# sensors.net
KiCad netlist of a schematic drawn in EAGLE
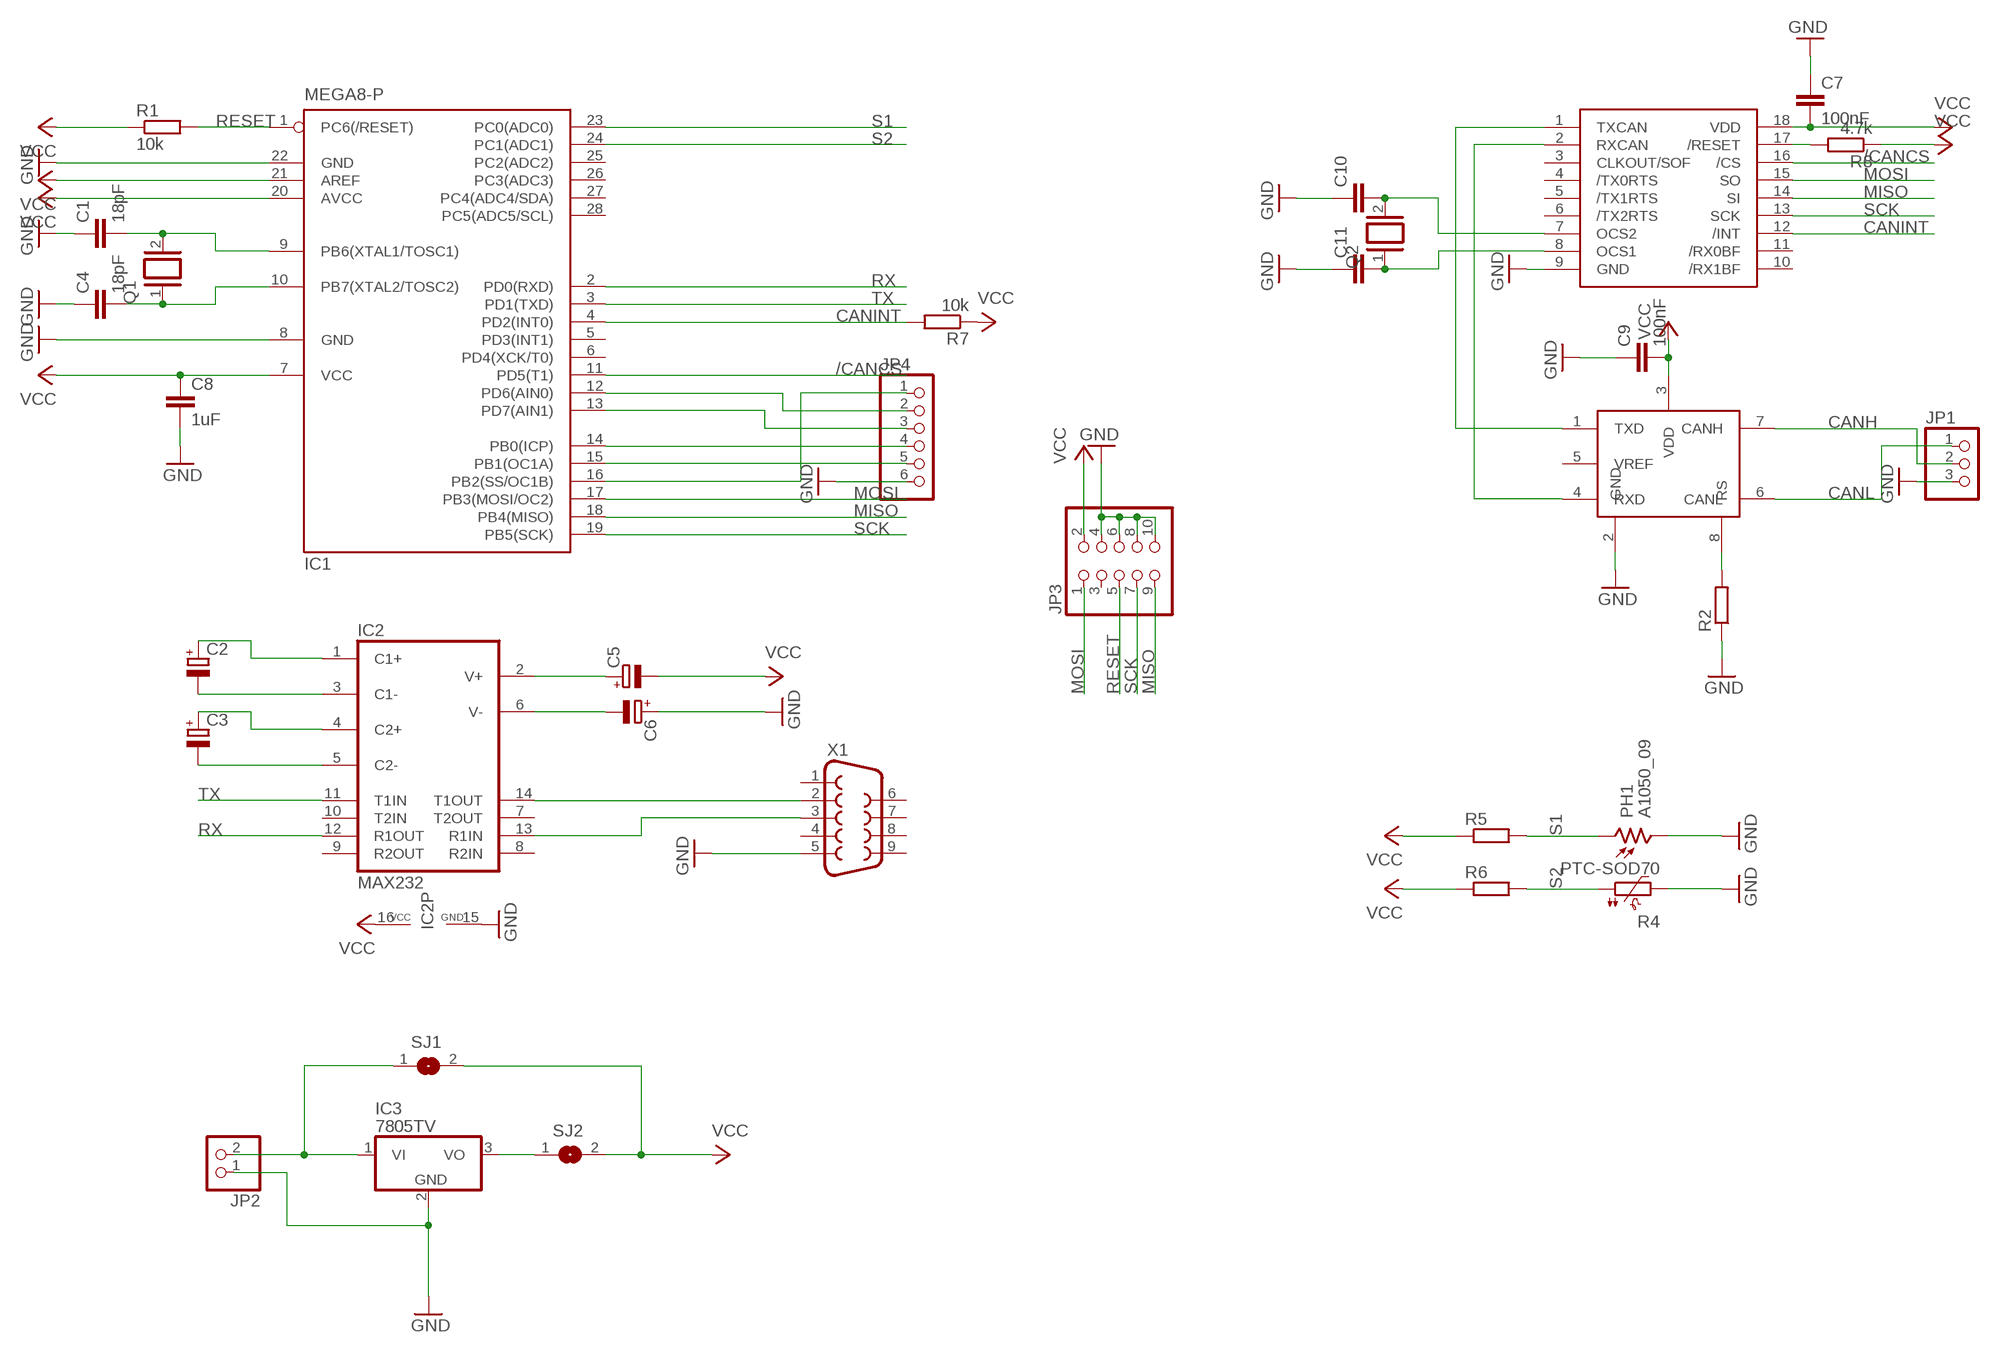
[diagram p0: schematic, sheet 1]

(export (version "E")
  (design (tool "Eeschema 10.0.6"))
  (components
    (comp (ref "C1")
      (value "18pF")
      (footprint "eagle-import:C025-024X044")
      (libsource (lib "eagle-import") (part "resistor_C-EU025-024X044"))
    )
    (comp (ref "C2")
      (value "CPOL-EUE3.5-8")
      (footprint "eagle-import:E3,5-8")
      (libsource (lib "eagle-import") (part "CPOL-EUE3.5-8"))
    )
    (comp (ref "C3")
      (value "CPOL-EUE3.5-8")
      (footprint "eagle-import:E3,5-8")
      (libsource (lib "eagle-import") (part "CPOL-EUE3.5-8"))
    )
    (comp (ref "C4")
      (value "18pF")
      (footprint "eagle-import:C025-024X044")
      (libsource (lib "eagle-import") (part "resistor_C-EU025-024X044"))
    )
    (comp (ref "C5")
      (value "CPOL-EUE3.5-8")
      (footprint "eagle-import:E3,5-8")
      (libsource (lib "eagle-import") (part "CPOL-EUE3.5-8"))
    )
    (comp (ref "C6")
      (value "CPOL-EUE3.5-8")
      (footprint "eagle-import:E3,5-8")
      (libsource (lib "eagle-import") (part "CPOL-EUE3.5-8"))
    )
    (comp (ref "C7")
      (value "100nF")
      (footprint "eagle-import:C0603")
      (libsource (lib "eagle-import") (part "C-EUC0603"))
    )
    (comp (ref "C8")
      (value "1uF")
      (footprint "eagle-import:C0603")
      (libsource (lib "eagle-import") (part "C-EUC0603"))
    )
    (comp (ref "C9")
      (value "100nF")
      (footprint "eagle-import:C0603")
      (libsource (lib "eagle-import") (part "C-EUC0603"))
    )
    (comp (ref "C10")
      (value "C-EUC0603")
      (footprint "eagle-import:C0603")
      (libsource (lib "eagle-import") (part "C-EUC0603"))
    )
    (comp (ref "C11")
      (value "C-EUC0603")
      (footprint "eagle-import:C0603")
      (libsource (lib "eagle-import") (part "C-EUC0603"))
    )
    (comp (ref "IC1")
      (value "MEGA8-P")
      (footprint "eagle-import:DIL28-3")
      (libsource (lib "eagle-import") (part "MEGA8-P"))
    )
    (comp (ref "IC2")
      (value "MAX232")
      (footprint "eagle-import:DIL16")
      (fields (field (name "MF") "MAXIM") (field (name "MPN") "MAX232ACPE+"))
      (libsource (lib "eagle-import") (part "MAX232"))
    )
    (comp (ref "IC3")
      (value "7805TV")
      (footprint "eagle-import:TO220V")
      (libsource (lib "eagle-import") (part "78TV05"))
    )
    (comp (ref "JP1")
      (value "PINHD-1X3")
      (footprint "eagle-import:1X03")
      (libsource (lib "eagle-import") (part "PINHD-1X3"))
    )
    (comp (ref "JP2")
      (value "PINHD-1X2")
      (footprint "eagle-import:1X02")
      (libsource (lib "eagle-import") (part "PINHD-1X2"))
    )
    (comp (ref "JP3")
      (value "PINHD-2X5")
      (footprint "eagle-import:2X05")
      (libsource (lib "eagle-import") (part "PINHD-2X5"))
    )
    (comp (ref "JP4")
      (value "PINHD-1X6")
      (footprint "eagle-import:1X06")
      (libsource (lib "eagle-import") (part "PINHD-1X6"))
    )
    (comp (ref "PH1")
      (value "A1050_09")
      (footprint "eagle-import:T0-46-A10XX")
      (libsource (lib "eagle-import") (part "A1050_09"))
    )
    (comp (ref "Q1")
      (value "XTAL/S")
      (footprint "eagle-import:QS")
      (libsource (lib "eagle-import") (part "XTAL/S"))
    )
    (comp (ref "Q2")
      (value "XTAL/S")
      (footprint "eagle-import:QS")
      (libsource (lib "eagle-import") (part "XTAL/S"))
    )
    (comp (ref "R1")
      (value "10k")
      (footprint "eagle-import:0207_10")
      (libsource (lib "eagle-import") (part "resistor_R-EU_0207/10"))
    )
    (comp (ref "R2")
      (value "R-EU_0207/10")
      (footprint "eagle-import:0207_10")
      (libsource (lib "eagle-import") (part "resistor_R-EU_0207/10"))
    )
    (comp (ref "R4")
      (value "PTC-SOD70")
      (footprint "eagle-import:SOD70")
      (libsource (lib "eagle-import") (part "PTC-SOD70"))
    )
    (comp (ref "R5")
      (value "R-EU_0207/10")
      (footprint "eagle-import:0207_10")
      (libsource (lib "eagle-import") (part "R-EU_0207/10"))
    )
    (comp (ref "R6")
      (value "R-EU_0207/10")
      (footprint "eagle-import:0207_10")
      (libsource (lib "eagle-import") (part "R-EU_0207/10"))
    )
    (comp (ref "R7")
      (value "10k")
      (footprint "eagle-import:0207_10")
      (libsource (lib "eagle-import") (part "resistor_R-EU_0207/10"))
    )
    (comp (ref "R8")
      (value "4.7k")
      (footprint "eagle-import:0207_10")
      (libsource (lib "eagle-import") (part "R-EU_0207/10"))
    )
    (comp (ref "SJ1") (value "SJ") (footprint "eagle-import:SJ") (libsource (lib "eagle-import") (part "SJ")))
    (comp (ref "SJ2") (value "SJ") (footprint "eagle-import:SJ") (libsource (lib "eagle-import") (part "SJ")))
    (comp (ref "U$1")
      (value "MCP251518-LEAD_SOIC")
      (footprint "eagle-import:SOIC18L")
      (libsource (lib "eagle-import") (part "MCP251518-LEAD_SOIC"))
    )
    (comp (ref "U$2")
      (value "MCP2551DIL8")
      (footprint "eagle-import:DIL8")
      (libsource (lib "eagle-import") (part "MCP2551DIL8"))
    )
    (comp (ref "X1")
      (value "F09HP")
      (footprint "eagle-import:F09HP")
      (libsource (lib "eagle-import") (part "F09HP"))
    )
  )
  (nets
    (net (code "1") (name "/CANH") (class "Default")
      (node (ref "JP1") (pin "2") (pinfunction "2_2") (pintype "passive"))
      (node (ref "U$2") (pin "7") (pinfunction "CANH_7") (pintype "bidirectional"))
    )
    (net (code "2") (name "/CANINT") (class "Default")
      (node (ref "IC1") (pin "4") (pinfunction "PD2(INT0)_4") (pintype "bidirectional"))
      (node (ref "R7") (pin "2") (pinfunction "2_2") (pintype "passive"))
      (node (ref "U$1") (pin "12") (pinfunction "/INT_12") (pintype "bidirectional"))
    )
    (net (code "3") (name "/CANL") (class "Default")
      (node (ref "JP1") (pin "1") (pinfunction "1_1") (pintype "passive"))
      (node (ref "U$2") (pin "6") (pinfunction "CANL_6") (pintype "bidirectional"))
    )
    (net (code "4") (name "/MISO") (class "Default")
      (node (ref "IC1") (pin "18") (pinfunction "PB4(MISO)_18") (pintype "bidirectional"))
      (node (ref "JP3") (pin "9") (pinfunction "9_9") (pintype "passive"))
      (node (ref "U$1") (pin "14") (pinfunction "SI_14") (pintype "bidirectional"))
    )
    (net (code "5") (name "/MOSI") (class "Default")
      (node (ref "IC1") (pin "17") (pinfunction "PB3(MOSI/OC2)_17") (pintype "bidirectional"))
      (node (ref "JP3") (pin "1") (pinfunction "1_1") (pintype "passive"))
      (node (ref "U$1") (pin "15") (pinfunction "SO_15") (pintype "bidirectional"))
    )
    (net (code "6") (name "/RESET") (class "Default")
      (node (ref "IC1") (pin "1") (pinfunction "PC6(/RESET)_1") (pintype "bidirectional"))
      (node (ref "JP3") (pin "5") (pinfunction "5_5") (pintype "passive"))
      (node (ref "R1") (pin "2") (pinfunction "2_2") (pintype "passive"))
    )
    (net (code "7") (name "/RX") (class "Default")
      (node (ref "IC1") (pin "2") (pinfunction "PD0(RXD)_2") (pintype "bidirectional"))
      (node (ref "IC2") (pin "12") (pinfunction "R1OUT_12") (pintype "output"))
    )
    (net (code "8") (name "/S1") (class "Default")
      (node (ref "IC1") (pin "23") (pinfunction "PC0(ADC0)_23") (pintype "bidirectional"))
      (node (ref "PH1") (pin "1") (pinfunction "1_1") (pintype "passive"))
      (node (ref "R5") (pin "2") (pinfunction "2_2") (pintype "passive"))
    )
    (net (code "9") (name "/S2") (class "Default")
      (node (ref "IC1") (pin "24") (pinfunction "PC1(ADC1)_24") (pintype "bidirectional"))
      (node (ref "R4") (pin "1") (pinfunction "1_1") (pintype "passive"))
      (node (ref "R6") (pin "2") (pinfunction "2_2") (pintype "passive"))
    )
    (net (code "10") (name "/SCK") (class "Default")
      (node (ref "IC1") (pin "19") (pinfunction "PB5(SCK)_19") (pintype "bidirectional"))
      (node (ref "JP3") (pin "7") (pinfunction "7_7") (pintype "passive"))
      (node (ref "U$1") (pin "13") (pinfunction "SCK_13") (pintype "bidirectional"))
    )
    (net (code "11") (name "/TX") (class "Default")
      (node (ref "IC1") (pin "3") (pinfunction "PD1(TXD)_3") (pintype "bidirectional"))
      (node (ref "IC2") (pin "11") (pinfunction "T1IN_11") (pintype "input"))
    )
    (net (code "12") (name "/{slash}CANCS") (class "Default")
      (node (ref "IC1") (pin "11") (pinfunction "PD5(T1)_11") (pintype "bidirectional"))
      (node (ref "U$1") (pin "16") (pinfunction "/CS_16") (pintype "bidirectional"))
    )
    (net (code "13") (name "GND") (class "Default")
      (node (ref "C1") (pin "1") (pinfunction "1_1") (pintype "passive"))
      (node (ref "C10") (pin "1") (pinfunction "1_1") (pintype "passive"))
      (node (ref "C11") (pin "1") (pinfunction "1_1") (pintype "passive"))
      (node (ref "C4") (pin "1") (pinfunction "1_1") (pintype "passive"))
      (node (ref "C6") (pin "+") (pinfunction "+_+") (pintype "passive"))
      (node (ref "C7") (pin "1") (pinfunction "1_1") (pintype "passive"))
      (node (ref "C8") (pin "2") (pinfunction "2_2") (pintype "passive"))
      (node (ref "C9") (pin "1") (pinfunction "1_1") (pintype "passive"))
      (node (ref "IC1") (pin "22") (pinfunction "GND_22") (pintype "power_in"))
      (node (ref "IC1") (pin "8") (pinfunction "GND_8") (pintype "power_in"))
      (node (ref "IC2") (pin "15") (pinfunction "GND_15") (pintype "power_in"))
      (node (ref "IC3") (pin "2") (pinfunction "GND_2") (pintype "passive"))
      (node (ref "JP1") (pin "3") (pinfunction "3_3") (pintype "passive"))
      (node (ref "JP2") (pin "1") (pinfunction "1_1") (pintype "passive"))
      (node (ref "JP3") (pin "10") (pinfunction "10_10") (pintype "passive"))
      (node (ref "JP3") (pin "4") (pinfunction "4_4") (pintype "passive"))
      (node (ref "JP3") (pin "6") (pinfunction "6_6") (pintype "passive"))
      (node (ref "JP3") (pin "8") (pinfunction "8_8") (pintype "passive"))
      (node (ref "JP4") (pin "6") (pinfunction "6_6") (pintype "passive"))
      (node (ref "PH1") (pin "2") (pinfunction "2_2") (pintype "passive"))
      (node (ref "R2") (pin "1") (pinfunction "1_1") (pintype "passive"))
      (node (ref "R4") (pin "2") (pinfunction "2_2") (pintype "passive"))
      (node (ref "U$1") (pin "9") (pinfunction "GND_9") (pintype "bidirectional"))
      (node (ref "U$2") (pin "2") (pinfunction "GND_2") (pintype "bidirectional"))
      (node (ref "X1") (pin "5") (pinfunction "5_5") (pintype "passive"))
    )
    (net (code "14") (name "Net-(IC1-PB0(ICP))") (class "Default")
      (node (ref "IC1") (pin "14") (pinfunction "PB0(ICP)_14") (pintype "bidirectional"))
      (node (ref "JP4") (pin "4") (pinfunction "4_4") (pintype "passive"))
    )
    (net (code "15") (name "Net-(IC1-PB1(OC1A))") (class "Default")
      (node (ref "IC1") (pin "15") (pinfunction "PB1(OC1A)_15") (pintype "bidirectional"))
      (node (ref "JP4") (pin "5") (pinfunction "5_5") (pintype "passive"))
    )
    (net (code "16") (name "Net-(IC1-PB2(SS{slash}OC1B))") (class "Default")
      (node (ref "IC1") (pin "16") (pinfunction "PB2(SS/OC1B)_16") (pintype "bidirectional"))
      (node (ref "JP4") (pin "1") (pinfunction "1_1") (pintype "passive"))
    )
    (net (code "17") (name "Net-(IC1-PB6(XTAL1{slash}TOSC1))") (class "Default")
      (node (ref "C1") (pin "2") (pinfunction "2_2") (pintype "passive"))
      (node (ref "IC1") (pin "9") (pinfunction "PB6(XTAL1/TOSC1)_9") (pintype "bidirectional"))
      (node (ref "Q1") (pin "2") (pinfunction "2_2") (pintype "passive"))
    )
    (net (code "18") (name "Net-(IC1-PB7(XTAL2{slash}TOSC2))") (class "Default")
      (node (ref "C4") (pin "2") (pinfunction "2_2") (pintype "passive"))
      (node (ref "IC1") (pin "10") (pinfunction "PB7(XTAL2/TOSC2)_10") (pintype "bidirectional"))
      (node (ref "Q1") (pin "1") (pinfunction "1_1") (pintype "passive"))
    )
    (net (code "19") (name "Net-(IC1-PD6(AIN0))") (class "Default")
      (node (ref "IC1") (pin "12") (pinfunction "PD6(AIN0)_12") (pintype "bidirectional"))
      (node (ref "JP4") (pin "2") (pinfunction "2_2") (pintype "passive"))
    )
    (net (code "20") (name "Net-(IC1-PD7(AIN1))") (class "Default")
      (node (ref "IC1") (pin "13") (pinfunction "PD7(AIN1)_13") (pintype "bidirectional"))
      (node (ref "JP4") (pin "3") (pinfunction "3_3") (pintype "passive"))
    )
    (net (code "21") (name "Net-(IC2A-C1+)") (class "Default")
      (node (ref "C2") (pin "+") (pinfunction "+_+") (pintype "passive"))
      (node (ref "IC2") (pin "1") (pinfunction "C1+_1") (pintype "bidirectional"))
    )
    (net (code "22") (name "Net-(IC2A-C1-)") (class "Default")
      (node (ref "C2") (pin "-") (pinfunction "-_-") (pintype "passive"))
      (node (ref "IC2") (pin "3") (pinfunction "C1-_3") (pintype "bidirectional"))
    )
    (net (code "23") (name "Net-(IC2A-C2+)") (class "Default")
      (node (ref "C3") (pin "+") (pinfunction "+_+") (pintype "passive"))
      (node (ref "IC2") (pin "4") (pinfunction "C2+_4") (pintype "bidirectional"))
    )
    (net (code "24") (name "Net-(IC2A-C2-)") (class "Default")
      (node (ref "C3") (pin "-") (pinfunction "-_-") (pintype "passive"))
      (node (ref "IC2") (pin "5") (pinfunction "C2-_5") (pintype "bidirectional"))
    )
    (net (code "25") (name "Net-(IC2A-R1IN)") (class "Default")
      (node (ref "IC2") (pin "13") (pinfunction "R1IN_13") (pintype "input"))
      (node (ref "X1") (pin "3") (pinfunction "3_3") (pintype "passive"))
    )
    (net (code "26") (name "Net-(IC2A-T1OUT)") (class "Default")
      (node (ref "IC2") (pin "14") (pinfunction "T1OUT_14") (pintype "output"))
      (node (ref "X1") (pin "2") (pinfunction "2_2") (pintype "passive"))
    )
    (net (code "27") (name "Net-(IC2A-V+)") (class "Default")
      (node (ref "C5") (pin "+") (pinfunction "+_+") (pintype "passive"))
      (node (ref "IC2") (pin "2") (pinfunction "V+_2") (pintype "bidirectional"))
    )
    (net (code "28") (name "Net-(IC2A-V-)") (class "Default")
      (node (ref "C6") (pin "-") (pinfunction "-_-") (pintype "passive"))
      (node (ref "IC2") (pin "6") (pinfunction "V-_6") (pintype "bidirectional"))
    )
    (net (code "29") (name "Net-(IC3-VI)") (class "Default")
      (node (ref "IC3") (pin "1") (pinfunction "VI_1") (pintype "input"))
      (node (ref "JP2") (pin "2") (pinfunction "2_2") (pintype "passive"))
      (node (ref "SJ1") (pin "1") (pinfunction "1_1") (pintype "passive"))
    )
    (net (code "30") (name "Net-(IC3-VO)") (class "Default")
      (node (ref "IC3") (pin "3") (pinfunction "VO_3") (pintype "passive"))
      (node (ref "SJ2") (pin "1") (pinfunction "1_1") (pintype "passive"))
    )
    (net (code "31") (name "Net-(U$1-OCS1)") (class "Default")
      (node (ref "C11") (pin "2") (pinfunction "2_2") (pintype "passive"))
      (node (ref "Q2") (pin "1") (pinfunction "1_1") (pintype "passive"))
      (node (ref "U$1") (pin "8") (pinfunction "OCS1_8") (pintype "bidirectional"))
    )
    (net (code "32") (name "Net-(U$1-OCS2)") (class "Default")
      (node (ref "C10") (pin "2") (pinfunction "2_2") (pintype "passive"))
      (node (ref "Q2") (pin "2") (pinfunction "2_2") (pintype "passive"))
      (node (ref "U$1") (pin "7") (pinfunction "OCS2_7") (pintype "bidirectional"))
    )
    (net (code "33") (name "Net-(U$1-RXCAN)") (class "Default")
      (node (ref "U$1") (pin "2") (pinfunction "RXCAN_2") (pintype "bidirectional"))
      (node (ref "U$2") (pin "4") (pinfunction "RXD_4") (pintype "bidirectional"))
    )
    (net (code "34") (name "Net-(U$1-TXCAN)") (class "Default")
      (node (ref "U$1") (pin "1") (pinfunction "TXCAN_1") (pintype "bidirectional"))
      (node (ref "U$2") (pin "1") (pinfunction "TXD_1") (pintype "bidirectional"))
    )
    (net (code "35") (name "Net-(U$1-{slash}RESET)") (class "Default")
      (node (ref "R8") (pin "2") (pinfunction "2_2") (pintype "passive"))
      (node (ref "U$1") (pin "17") (pinfunction "/RESET_17") (pintype "bidirectional"))
    )
    (net (code "36") (name "Net-(U$2-RS)") (class "Default")
      (node (ref "R2") (pin "2") (pinfunction "2_2") (pintype "passive"))
      (node (ref "U$2") (pin "8") (pinfunction "RS_8") (pintype "bidirectional"))
    )
    (net (code "37") (name "VCC") (class "Default")
      (node (ref "C5") (pin "-") (pinfunction "-_-") (pintype "passive"))
      (node (ref "C7") (pin "2") (pinfunction "2_2") (pintype "passive"))
      (node (ref "C8") (pin "1") (pinfunction "1_1") (pintype "passive"))
      (node (ref "C9") (pin "2") (pinfunction "2_2") (pintype "passive"))
      (node (ref "IC1") (pin "20") (pinfunction "AVCC_20") (pintype "power_in"))
      (node (ref "IC1") (pin "21") (pinfunction "AREF_21") (pintype "passive"))
      (node (ref "IC1") (pin "7") (pinfunction "VCC_7") (pintype "power_in"))
      (node (ref "IC2") (pin "16") (pinfunction "VCC_16") (pintype "power_in"))
      (node (ref "JP3") (pin "2") (pinfunction "2_2") (pintype "passive"))
      (node (ref "R1") (pin "1") (pinfunction "1_1") (pintype "passive"))
      (node (ref "R5") (pin "1") (pinfunction "1_1") (pintype "passive"))
      (node (ref "R6") (pin "1") (pinfunction "1_1") (pintype "passive"))
      (node (ref "R7") (pin "1") (pinfunction "1_1") (pintype "passive"))
      (node (ref "R8") (pin "1") (pinfunction "1_1") (pintype "passive"))
      (node (ref "SJ1") (pin "2") (pinfunction "2_2") (pintype "passive"))
      (node (ref "SJ2") (pin "2") (pinfunction "2_2") (pintype "passive"))
      (node (ref "U$1") (pin "18") (pinfunction "VDD_18") (pintype "bidirectional"))
      (node (ref "U$2") (pin "3") (pinfunction "VDD_3") (pintype "bidirectional"))
    )
    (net (code "38") (name "unconnected-(IC1-PC2(ADC2)-Pad25)") (class "Default")
      (node (ref "IC1") (pin "25") (pinfunction "PC2(ADC2)_25") (pintype "bidirectional"))
    )
    (net (code "39") (name "unconnected-(IC1-PC3(ADC3)-Pad26)") (class "Default")
      (node (ref "IC1") (pin "26") (pinfunction "PC3(ADC3)_26") (pintype "bidirectional"))
    )
    (net (code "40") (name "unconnected-(IC1-PC4(ADC4{slash}SDA)-Pad27)") (class "Default")
      (node (ref "IC1") (pin "27") (pinfunction "PC4(ADC4/SDA)_27") (pintype "bidirectional"))
    )
    (net (code "41") (name "unconnected-(IC1-PC5(ADC5{slash}SCL)-Pad28)") (class "Default")
      (node (ref "IC1") (pin "28") (pinfunction "PC5(ADC5/SCL)_28") (pintype "bidirectional"))
    )
    (net (code "42") (name "unconnected-(IC1-PD3(INT1)-Pad5)") (class "Default")
      (node (ref "IC1") (pin "5") (pinfunction "PD3(INT1)_5") (pintype "bidirectional"))
    )
    (net (code "43") (name "unconnected-(IC1-PD4(XCK{slash}T0)-Pad6)") (class "Default")
      (node (ref "IC1") (pin "6") (pinfunction "PD4(XCK/T0)_6") (pintype "bidirectional"))
    )
    (net (code "44") (name "unconnected-(IC2A-R2IN-Pad8)") (class "Default")
      (node (ref "IC2") (pin "8") (pinfunction "R2IN_8") (pintype "input"))
    )
    (net (code "45") (name "unconnected-(IC2A-R2OUT-Pad9)") (class "Default")
      (node (ref "IC2") (pin "9") (pinfunction "R2OUT_9") (pintype "output"))
    )
    (net (code "46") (name "unconnected-(IC2A-T2IN-Pad10)") (class "Default")
      (node (ref "IC2") (pin "10") (pinfunction "T2IN_10") (pintype "input"))
    )
    (net (code "47") (name "unconnected-(IC2A-T2OUT-Pad7)") (class "Default")
      (node (ref "IC2") (pin "7") (pinfunction "T2OUT_7") (pintype "output"))
    )
    (net (code "48") (name "unconnected-(JP3-Pad3)") (class "Default")
      (node (ref "JP3") (pin "3") (pinfunction "3_3") (pintype "passive"))
    )
    (net (code "49") (name "unconnected-(U$1-CLKOUT{slash}SOF-Pad3)") (class "Default")
      (node (ref "U$1") (pin "3") (pinfunction "CLKOUT/SOF_3") (pintype "bidirectional"))
    )
    (net (code "50") (name "unconnected-(U$1-{slash}RX0BF-Pad11)") (class "Default")
      (node (ref "U$1") (pin "11") (pinfunction "/RX0BF_11") (pintype "bidirectional"))
    )
    (net (code "51") (name "unconnected-(U$1-{slash}RX1BF-Pad10)") (class "Default")
      (node (ref "U$1") (pin "10") (pinfunction "/RX1BF_10") (pintype "bidirectional"))
    )
    (net (code "52") (name "unconnected-(U$1-{slash}TX0RTS-Pad4)") (class "Default")
      (node (ref "U$1") (pin "4") (pinfunction "/TX0RTS_4") (pintype "bidirectional"))
    )
    (net (code "53") (name "unconnected-(U$1-{slash}TX1RTS-Pad5)") (class "Default")
      (node (ref "U$1") (pin "5") (pinfunction "/TX1RTS_5") (pintype "bidirectional"))
    )
    (net (code "54") (name "unconnected-(U$1-{slash}TX2RTS-Pad6)") (class "Default")
      (node (ref "U$1") (pin "6") (pinfunction "/TX2RTS_6") (pintype "bidirectional"))
    )
    (net (code "55") (name "unconnected-(U$2-VREF-Pad5)") (class "Default")
      (node (ref "U$2") (pin "5") (pinfunction "VREF_5") (pintype "bidirectional"))
    )
    (net (code "56") (name "unconnected-(X1-Pad1)") (class "Default")
      (node (ref "X1") (pin "1") (pinfunction "1_1") (pintype "passive"))
    )
    (net (code "57") (name "unconnected-(X1-Pad4)") (class "Default")
      (node (ref "X1") (pin "4") (pinfunction "4_4") (pintype "passive"))
    )
    (net (code "58") (name "unconnected-(X1-Pad6)") (class "Default")
      (node (ref "X1") (pin "6") (pinfunction "6_6") (pintype "passive"))
    )
    (net (code "59") (name "unconnected-(X1-Pad7)") (class "Default")
      (node (ref "X1") (pin "7") (pinfunction "7_7") (pintype "passive"))
    )
    (net (code "60") (name "unconnected-(X1-Pad8)") (class "Default")
      (node (ref "X1") (pin "8") (pinfunction "8_8") (pintype "passive"))
    )
    (net (code "61") (name "unconnected-(X1-Pad9)") (class "Default")
      (node (ref "X1") (pin "9") (pinfunction "9_9") (pintype "passive"))
    )
  )
)
